# BMP180.net
KiCad netlist of a schematic drawn in Altium Designer
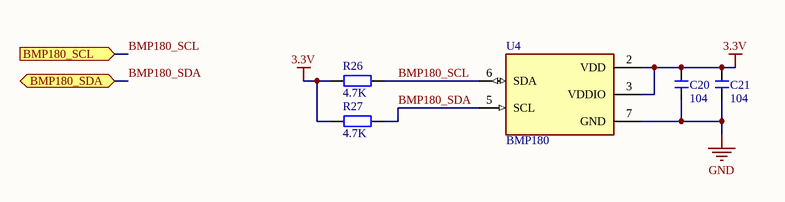
[diagram p0: BMP180气压传感器模块.SchDoc]

(export (version "E")
  (design (tool "Eeschema 10.0.6"))
  (components
    (comp (ref "C20")
      (value "104")
      (footprint "C 0603_L")
      (description "无极性贴片电容")
      (fields (field (name "版权归属") "黎明电子style"))
      (libsource (lib "3.3   - 电容capacitor") (part "C"))
    )
    (comp (ref "C21")
      (value "104")
      (footprint "C 0603_L")
      (description "无极性贴片电容")
      (fields (field (name "版权归属") "黎明电子style"))
      (libsource (lib "3.3   - 电容capacitor") (part "C"))
    )
    (comp (ref "R26")
      (value "4.7K")
      (footprint "R 0603_L")
      (description "贴片电阻")
      (fields (field (name "版权归属") "黎明电子style"))
      (libsource (lib "3.4   - 电阻Resistor") (part "R"))
    )
    (comp (ref "R27")
      (value "4.7K")
      (footprint "R 0603_L")
      (description "贴片电阻")
      (fields (field (name "版权归属") "黎明电子style"))
      (libsource (lib "3.4   - 电阻Resistor") (part "R"))
    )
    (comp (ref "U4")
      (value "BMP180")
      (footprint "LGA:LGA-7")
      (description "气压传感器Pressure Sensor 4.35PSI ~ 15.95PSI _30kPa ~ 110kPa_ Absolute 16 ~ 19 b 7-VLGA")
      (fields (field (name "MF") "Bosch Sensortec") (field (name "DIGI-KEY_PART_NUMBER") "828-1027-1-ND"))
      (libsource (lib "11.1 - 传感元件") (part "BMP180"))
    )
  )
  (nets
    (net (code "1") (name "/BMP180_SCL") (class "Default")
      (node (ref "R26") (pin "1") (pinfunction "1_1") (pintype "passive"))
      (node (ref "U4") (pin "6") (pinfunction "SDA_6") (pintype "bidirectional"))
    )
    (net (code "2") (name "/BMP180_SDA") (class "Default")
      (node (ref "R27") (pin "1") (pinfunction "1_1") (pintype "passive"))
      (node (ref "U4") (pin "5") (pinfunction "SCL_5") (pintype "input"))
    )
    (net (code "3") (name "3.3V") (class "Default")
      (node (ref "C20") (pin "2") (pinfunction "2_2") (pintype "passive"))
      (node (ref "C21") (pin "2") (pinfunction "2_2") (pintype "passive"))
      (node (ref "R26") (pin "2") (pinfunction "2_2") (pintype "passive"))
      (node (ref "R27") (pin "2") (pinfunction "2_2") (pintype "passive"))
      (node (ref "U4") (pin "2") (pinfunction "VDD_2") (pintype "power_in"))
      (node (ref "U4") (pin "3") (pinfunction "VDDIO_3") (pintype "power_in"))
    )
    (net (code "4") (name "GND") (class "Default")
      (node (ref "C20") (pin "1") (pinfunction "1_1") (pintype "passive"))
      (node (ref "C21") (pin "1") (pinfunction "1_1") (pintype "passive"))
      (node (ref "U4") (pin "7") (pinfunction "GND_7") (pintype "power_in"))
    )
  )
)
